# YamakenMusicPlayer.net
KiCad netlist of a schematic drawn in EAGLE
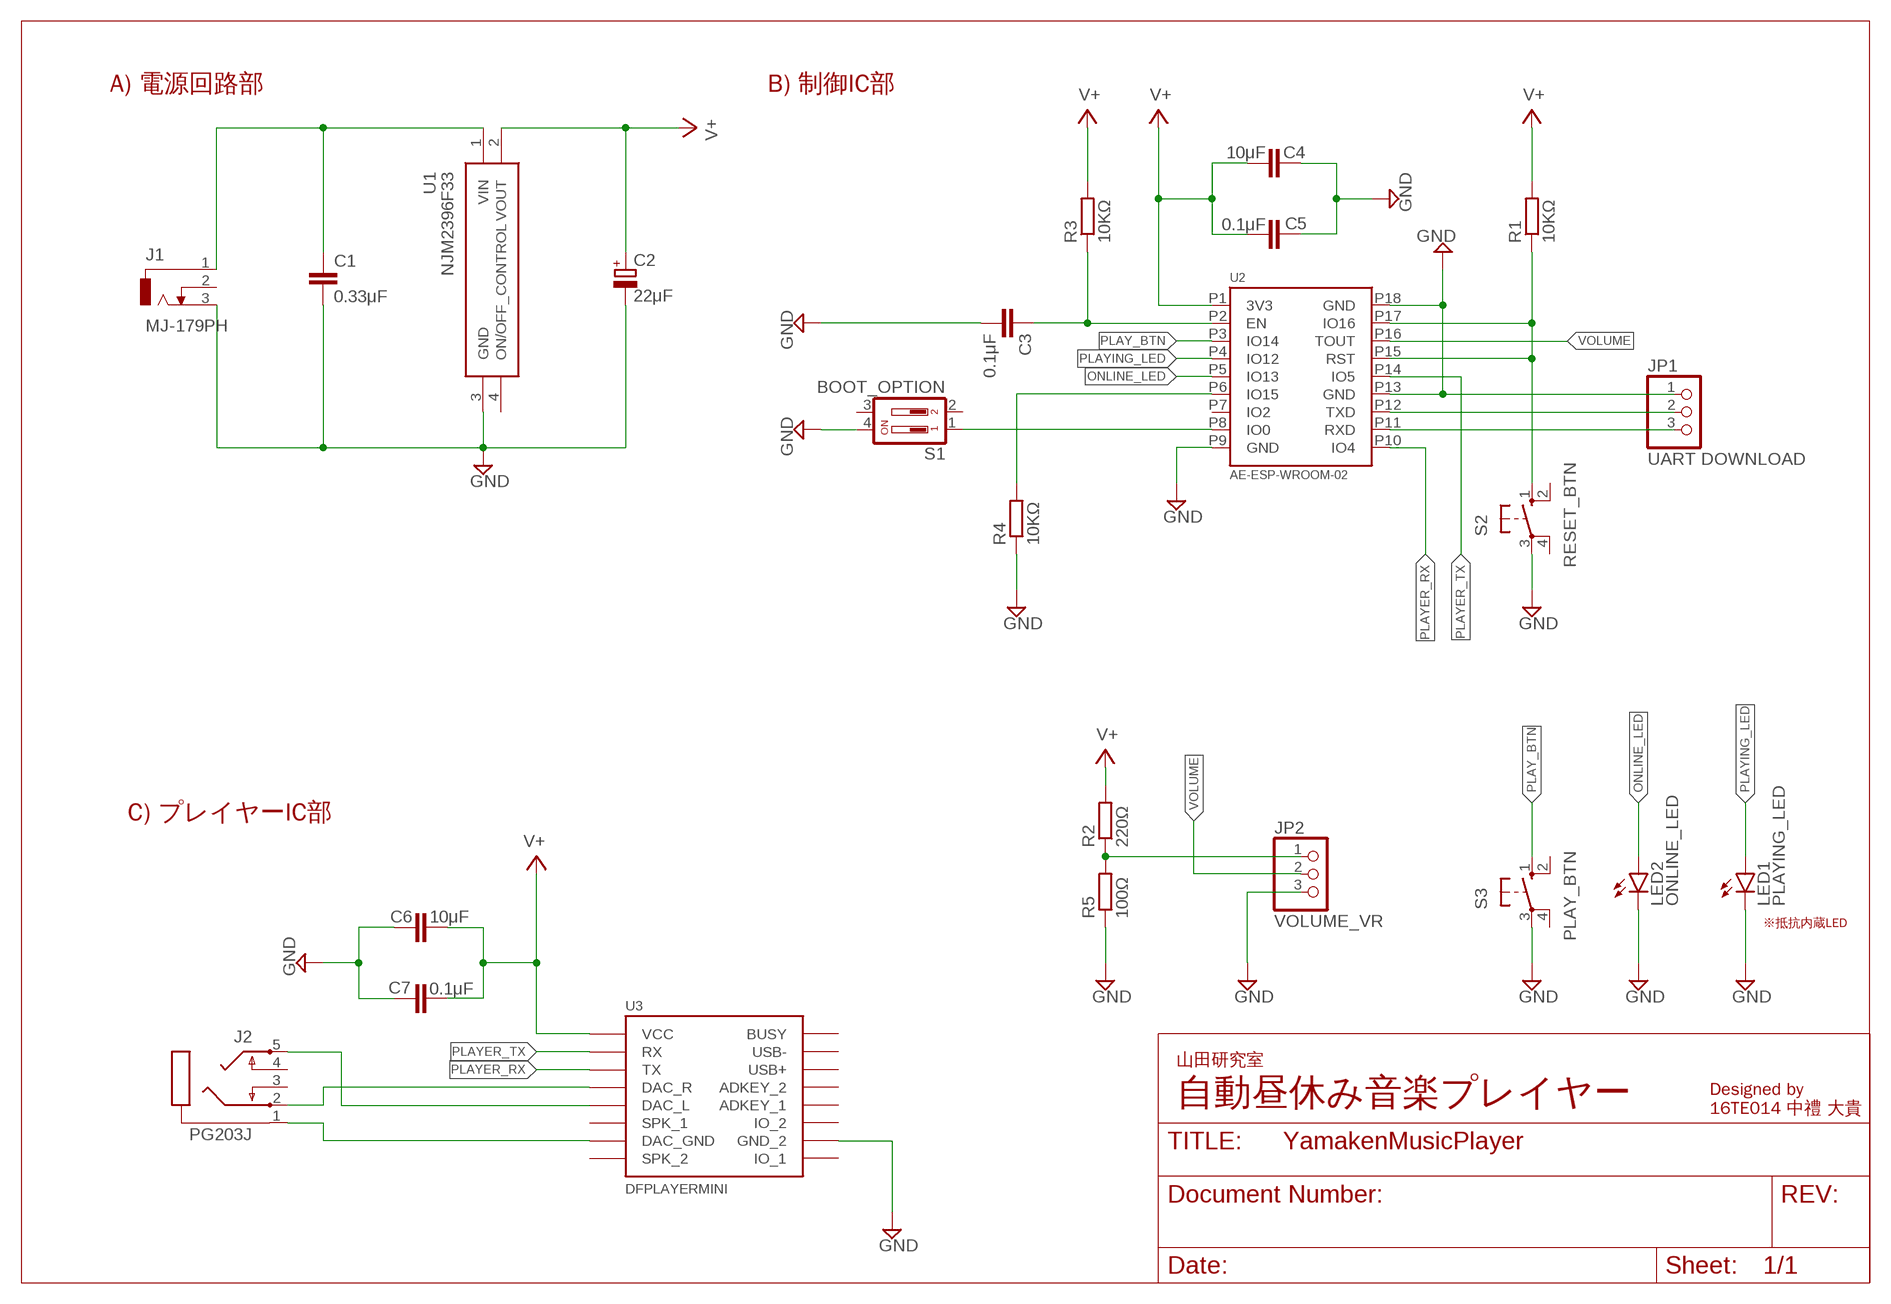
[diagram p0: schematic, sheet 1]

(export (version "E")
  (design (tool "Eeschema 10.0.6"))
  (components
    (comp (ref "C1")
      (value "0.33μF")
      (footprint "eagle-import:C050-024X044")
      (libsource (lib "eagle-import") (part "C-EU050-024X044"))
    )
    (comp (ref "C2")
      (value "22μF")
      (footprint "eagle-import:E2,5-7")
      (libsource (lib "eagle-import") (part "CPOL-EUE2.5-7"))
    )
    (comp (ref "C3")
      (value "0.1μF")
      (footprint "eagle-import:C050-024X044")
      (libsource (lib "eagle-import") (part "C-EU050-024X044"))
    )
    (comp (ref "C4")
      (value "10μF")
      (footprint "eagle-import:C050-024X044")
      (libsource (lib "eagle-import") (part "C-EU050-024X044"))
    )
    (comp (ref "C5")
      (value "0.1μF")
      (footprint "eagle-import:C050-024X044")
      (libsource (lib "eagle-import") (part "C-EU050-024X044"))
    )
    (comp (ref "C6")
      (value "10μF")
      (footprint "eagle-import:C050-024X044")
      (libsource (lib "eagle-import") (part "C-EU050-024X044"))
    )
    (comp (ref "C7")
      (value "0.1μF")
      (footprint "eagle-import:C050-024X044")
      (libsource (lib "eagle-import") (part "C-EU050-024X044"))
    )
    (comp (ref "J1")
      (value "MJ-179PH")
      (footprint "eagle-import:DCJ0202")
      (libsource (lib "eagle-import") (part "DCJ0202"))
    )
    (comp (ref "J2")
      (value "PG203J")
      (footprint "eagle-import:PG203J")
      (libsource (lib "eagle-import") (part "PG203J"))
    )
    (comp (ref "JP1")
      (value "UART DOWNLOAD")
      (footprint "eagle-import:1X03")
      (libsource (lib "eagle-import") (part "PINHD-1X3"))
    )
    (comp (ref "JP2")
      (value "VOLUME_VR")
      (footprint "eagle-import:1X03")
      (libsource (lib "eagle-import") (part "PINHD-1X3"))
    )
    (comp (ref "LED1")
      (value "PLAYING_LED")
      (footprint "eagle-import:LED5MM")
      (libsource (lib "eagle-import") (part "LED5MM"))
    )
    (comp (ref "LED2")
      (value "ONLINE_LED")
      (footprint "eagle-import:LED5MM")
      (libsource (lib "eagle-import") (part "LED5MM"))
    )
    (comp (ref "R1")
      (value "10KΩ")
      (footprint "eagle-import:0207_10")
      (libsource (lib "eagle-import") (part "R-EU_0207/10"))
    )
    (comp (ref "R2")
      (value "220Ω")
      (footprint "eagle-import:0207_10")
      (libsource (lib "eagle-import") (part "R-EU_0207/10"))
    )
    (comp (ref "R3")
      (value "10KΩ")
      (footprint "eagle-import:0207_10")
      (libsource (lib "eagle-import") (part "R-EU_0207/10"))
    )
    (comp (ref "R4")
      (value "10KΩ")
      (footprint "eagle-import:0207_10")
      (libsource (lib "eagle-import") (part "R-EU_0207/10"))
    )
    (comp (ref "R5")
      (value "100Ω")
      (footprint "eagle-import:0207_10")
      (libsource (lib "eagle-import") (part "R-EU_0207/10"))
    )
    (comp (ref "S1")
      (value "BOOT_OPTION")
      (footprint "eagle-import:DIP02YL")
      (libsource (lib "eagle-import") (part "DIP02YL"))
    )
    (comp (ref "S2")
      (value "RESET_BTN")
      (footprint "eagle-import:B3F-10XX")
      (fields (field (name "MPN") "B3F-1000"))
      (libsource (lib "eagle-import") (part "10-XX"))
    )
    (comp (ref "S3")
      (value "PLAY_BTN")
      (footprint "eagle-import:B3F-10XX")
      (fields (field (name "MPN") "B3F-1000"))
      (libsource (lib "eagle-import") (part "10-XX"))
    )
    (comp (ref "U1")
      (value "NJM2396F33")
      (footprint "eagle-import:TO254P480X1000X1900-4P")
      (fields (field (name "RS_PART_NUMBER") "1782325"))
      (libsource (lib "eagle-import") (part "NJM2396F33"))
    )
    (comp (ref "U2")
      (value "AE-ESP-WROOM-02")
      (footprint "eagle-import:AE-ESP-WROOM-02")
      (libsource (lib "eagle-import") (part "AE-ESP-WROOM-02"))
    )
    (comp (ref "U3")
      (value "DFPLAYERMINI")
      (footprint "eagle-import:DFPLAYERMINI")
      (libsource (lib "eagle-import") (part "DFPLAYERMINI"))
    )
  )
  (nets
    (net (code "1") (name "GND") (class "Default")
      (node (ref "C1") (pin "2") (pinfunction "2_2") (pintype "passive"))
      (node (ref "C2") (pin "-") (pinfunction "-_-") (pintype "passive"))
      (node (ref "C3") (pin "2") (pinfunction "2_2") (pintype "passive"))
      (node (ref "C4") (pin "1") (pinfunction "1_1") (pintype "passive"))
      (node (ref "C5") (pin "1") (pinfunction "1_1") (pintype "passive"))
      (node (ref "C6") (pin "1") (pinfunction "1_1") (pintype "passive"))
      (node (ref "C7") (pin "1") (pinfunction "1_1") (pintype "passive"))
      (node (ref "J1") (pin "3") (pinfunction "3_3") (pintype "passive"))
      (node (ref "JP1") (pin "1") (pinfunction "1_1") (pintype "passive"))
      (node (ref "JP2") (pin "3") (pinfunction "3_3") (pintype "passive"))
      (node (ref "LED1") (pin "K") (pinfunction "C_K") (pintype "passive"))
      (node (ref "LED2") (pin "K") (pinfunction "C_K") (pintype "passive"))
      (node (ref "R4") (pin "1") (pinfunction "1_1") (pintype "passive"))
      (node (ref "R5") (pin "1") (pinfunction "1_1") (pintype "passive"))
      (node (ref "S1") (pin "4") (pinfunction "4_4") (pintype "passive"))
      (node (ref "S2") (pin "3") (pinfunction "P_3") (pintype "passive"))
      (node (ref "S3") (pin "3") (pinfunction "P_3") (pintype "passive"))
      (node (ref "U1") (pin "3") (pinfunction "GND_3") (pintype "bidirectional"))
      (node (ref "U2") (pin "P13") (pinfunction "GND_P13") (pintype "bidirectional"))
      (node (ref "U2") (pin "P18") (pinfunction "GND_P18") (pintype "bidirectional"))
      (node (ref "U2") (pin "P9") (pinfunction "GND_P9") (pintype "bidirectional"))
      (node (ref "U3") (pin "GND_2") (pinfunction "GND_2_GND_2") (pintype "bidirectional"))
    )
    (net (code "2") (name "Net-(J2-Pad2)") (class "Default")
      (node (ref "J2") (pin "2") (pinfunction "2_2") (pintype "passive"))
      (node (ref "U3") (pin "DAC_R") (pinfunction "DAC_R_DAC_R") (pintype "bidirectional"))
    )
    (net (code "3") (name "Net-(J2-Pad5)") (class "Default")
      (node (ref "J2") (pin "5") (pinfunction "5_5") (pintype "passive"))
      (node (ref "U3") (pin "DAC_L") (pinfunction "DAC_L_DAC_L") (pintype "bidirectional"))
    )
    (net (code "4") (name "Net-(JP2-Pad1)") (class "Default")
      (node (ref "JP2") (pin "1") (pinfunction "1_1") (pintype "passive"))
      (node (ref "R2") (pin "1") (pinfunction "1_1") (pintype "passive"))
      (node (ref "R5") (pin "2") (pinfunction "2_2") (pintype "passive"))
    )
    (net (code "5") (name "Net-(S2-S)") (class "Default")
      (node (ref "R1") (pin "1") (pinfunction "1_1") (pintype "passive"))
      (node (ref "S2") (pin "1") (pinfunction "S_1") (pintype "passive"))
      (node (ref "U2") (pin "P15") (pinfunction "RST_P15") (pintype "bidirectional"))
      (node (ref "U2") (pin "P17") (pinfunction "IO16_P17") (pintype "bidirectional"))
    )
    (net (code "6") (name "Net-(U1-VIN)") (class "Default")
      (node (ref "C1") (pin "1") (pinfunction "1_1") (pintype "passive"))
      (node (ref "J1") (pin "1") (pinfunction "1_1") (pintype "passive"))
      (node (ref "U1") (pin "1") (pinfunction "VIN_1") (pintype "bidirectional"))
    )
    (net (code "7") (name "Net-(U2-EN)") (class "Default")
      (node (ref "C3") (pin "1") (pinfunction "1_1") (pintype "passive"))
      (node (ref "R3") (pin "1") (pinfunction "1_1") (pintype "passive"))
      (node (ref "U2") (pin "P2") (pinfunction "EN_P2") (pintype "bidirectional"))
    )
    (net (code "8") (name "Net-(U2-IO0)") (class "Default")
      (node (ref "S1") (pin "1") (pinfunction "1_1") (pintype "passive"))
      (node (ref "U2") (pin "P8") (pinfunction "IO0_P8") (pintype "bidirectional"))
    )
    (net (code "9") (name "Net-(U2-IO15)") (class "Default")
      (node (ref "R4") (pin "2") (pinfunction "2_2") (pintype "passive"))
      (node (ref "U2") (pin "P6") (pinfunction "IO15_P6") (pintype "bidirectional"))
    )
    (net (code "10") (name "Net-(U2-RXD)") (class "Default")
      (node (ref "JP1") (pin "3") (pinfunction "3_3") (pintype "passive"))
      (node (ref "U2") (pin "P11") (pinfunction "RXD_P11") (pintype "bidirectional"))
    )
    (net (code "11") (name "Net-(U2-TXD)") (class "Default")
      (node (ref "JP1") (pin "2") (pinfunction "2_2") (pintype "passive"))
      (node (ref "U2") (pin "P12") (pinfunction "TXD_P12") (pintype "bidirectional"))
    )
    (net (code "12") (name "Net-(U3-DAC_GND)") (class "Default")
      (node (ref "J2") (pin "1") (pinfunction "1_1") (pintype "passive"))
      (node (ref "U3") (pin "GND_1") (pinfunction "DAC_GND_GND_1") (pintype "bidirectional"))
    )
    (net (code "13") (name "ONLINE_LED") (class "Default")
      (node (ref "LED2") (pin "A") (pinfunction "A_A") (pintype "passive"))
      (node (ref "U2") (pin "P5") (pinfunction "IO13_P5") (pintype "bidirectional"))
    )
    (net (code "14") (name "PLAYER_RX") (class "Default")
      (node (ref "U2") (pin "P10") (pinfunction "IO4_P10") (pintype "bidirectional"))
      (node (ref "U3") (pin "TX") (pinfunction "TX_TX") (pintype "bidirectional"))
    )
    (net (code "15") (name "PLAYER_TX") (class "Default")
      (node (ref "U2") (pin "P14") (pinfunction "IO5_P14") (pintype "bidirectional"))
      (node (ref "U3") (pin "RX") (pinfunction "RX_RX") (pintype "bidirectional"))
    )
    (net (code "16") (name "PLAYING_LED") (class "Default")
      (node (ref "LED1") (pin "A") (pinfunction "A_A") (pintype "passive"))
      (node (ref "U2") (pin "P4") (pinfunction "IO12_P4") (pintype "bidirectional"))
    )
    (net (code "17") (name "PLAY_BTN") (class "Default")
      (node (ref "S3") (pin "1") (pinfunction "S_1") (pintype "passive"))
      (node (ref "U2") (pin "P3") (pinfunction "IO14_P3") (pintype "bidirectional"))
    )
    (net (code "18") (name "V+") (class "Default")
      (node (ref "C2") (pin "+") (pinfunction "+_+") (pintype "passive"))
      (node (ref "C4") (pin "2") (pinfunction "2_2") (pintype "passive"))
      (node (ref "C5") (pin "2") (pinfunction "2_2") (pintype "passive"))
      (node (ref "C6") (pin "2") (pinfunction "2_2") (pintype "passive"))
      (node (ref "C7") (pin "2") (pinfunction "2_2") (pintype "passive"))
      (node (ref "R1") (pin "2") (pinfunction "2_2") (pintype "passive"))
      (node (ref "R2") (pin "2") (pinfunction "2_2") (pintype "passive"))
      (node (ref "R3") (pin "2") (pinfunction "2_2") (pintype "passive"))
      (node (ref "U1") (pin "2") (pinfunction "VOUT_2") (pintype "bidirectional"))
      (node (ref "U2") (pin "P1") (pinfunction "3V3_P1") (pintype "bidirectional"))
      (node (ref "U3") (pin "VCC") (pinfunction "VCC_VCC") (pintype "bidirectional"))
    )
    (net (code "19") (name "VOLUME") (class "Default")
      (node (ref "JP2") (pin "2") (pinfunction "2_2") (pintype "passive"))
      (node (ref "U2") (pin "P16") (pinfunction "TOUT_P16") (pintype "bidirectional"))
    )
    (net (code "20") (name "unconnected-(J1-Pad2)") (class "Default")
      (node (ref "J1") (pin "2") (pinfunction "2_2") (pintype "passive"))
    )
    (net (code "21") (name "unconnected-(J2-Pad3)") (class "Default")
      (node (ref "J2") (pin "3") (pinfunction "3_3") (pintype "passive"))
    )
    (net (code "22") (name "unconnected-(J2-Pad4)") (class "Default")
      (node (ref "J2") (pin "4") (pinfunction "4_4") (pintype "passive"))
    )
    (net (code "23") (name "unconnected-(S1-Pad2)") (class "Default")
      (node (ref "S1") (pin "2") (pinfunction "2_2") (pintype "passive"))
    )
    (net (code "24") (name "unconnected-(S1-Pad3)") (class "Default")
      (node (ref "S1") (pin "3") (pinfunction "3_3") (pintype "passive"))
    )
    (net (code "25") (name "unconnected-(S2-P1-Pad4)") (class "Default")
      (node (ref "S2") (pin "4") (pinfunction "P1_4") (pintype "passive"))
    )
    (net (code "26") (name "unconnected-(S2-S1-Pad2)") (class "Default")
      (node (ref "S2") (pin "2") (pinfunction "S1_2") (pintype "passive"))
    )
    (net (code "27") (name "unconnected-(S3-P1-Pad4)") (class "Default")
      (node (ref "S3") (pin "4") (pinfunction "P1_4") (pintype "passive"))
    )
    (net (code "28") (name "unconnected-(S3-S1-Pad2)") (class "Default")
      (node (ref "S3") (pin "2") (pinfunction "S1_2") (pintype "passive"))
    )
    (net (code "29") (name "unconnected-(U1-ON{slash}OFF_CONTROL-Pad4)") (class "Default")
      (node (ref "U1") (pin "4") (pinfunction "ON/OFF_CONTROL_4") (pintype "bidirectional"))
    )
    (net (code "30") (name "unconnected-(U2-IO2-PadP7)") (class "Default")
      (node (ref "U2") (pin "P7") (pinfunction "IO2_P7") (pintype "bidirectional"))
    )
    (net (code "31") (name "unconnected-(U3-ADKEY_1-PadADKEY1)") (class "Default")
      (node (ref "U3") (pin "ADKEY1") (pinfunction "ADKEY_1_ADKEY1") (pintype "bidirectional"))
    )
    (net (code "32") (name "unconnected-(U3-ADKEY_2-PadADKEY2)") (class "Default")
      (node (ref "U3") (pin "ADKEY2") (pinfunction "ADKEY_2_ADKEY2") (pintype "bidirectional"))
    )
    (net (code "33") (name "unconnected-(U3-IO_1-PadIO1)") (class "Default")
      (node (ref "U3") (pin "IO1") (pinfunction "IO_1_IO1") (pintype "bidirectional"))
    )
    (net (code "34") (name "unconnected-(U3-IO_2-PadIO2)") (class "Default")
      (node (ref "U3") (pin "IO2") (pinfunction "IO_2_IO2") (pintype "bidirectional"))
    )
    (net (code "35") (name "unconnected-(U3-PadBUSY)") (class "Default")
      (node (ref "U3") (pin "BUSY") (pinfunction "BUSY_BUSY") (pintype "bidirectional"))
    )
    (net (code "36") (name "unconnected-(U3-PadUSB+)") (class "Default")
      (node (ref "U3") (pin "USB+") (pinfunction "USB+_USB+") (pintype "bidirectional"))
    )
    (net (code "37") (name "unconnected-(U3-PadUSB-)") (class "Default")
      (node (ref "U3") (pin "USB-") (pinfunction "USB-_USB-") (pintype "bidirectional"))
    )
    (net (code "38") (name "unconnected-(U3-SPK_1-PadSPK1)") (class "Default")
      (node (ref "U3") (pin "SPK1") (pinfunction "SPK_1_SPK1") (pintype "bidirectional"))
    )
    (net (code "39") (name "unconnected-(U3-SPK_2-PadSPK2)") (class "Default")
      (node (ref "U3") (pin "SPK2") (pinfunction "SPK_2_SPK2") (pintype "bidirectional"))
    )
  )
)
